# PWR_P3V0_N3V0.net
KiCad netlist of a schematic drawn in Altium Designer
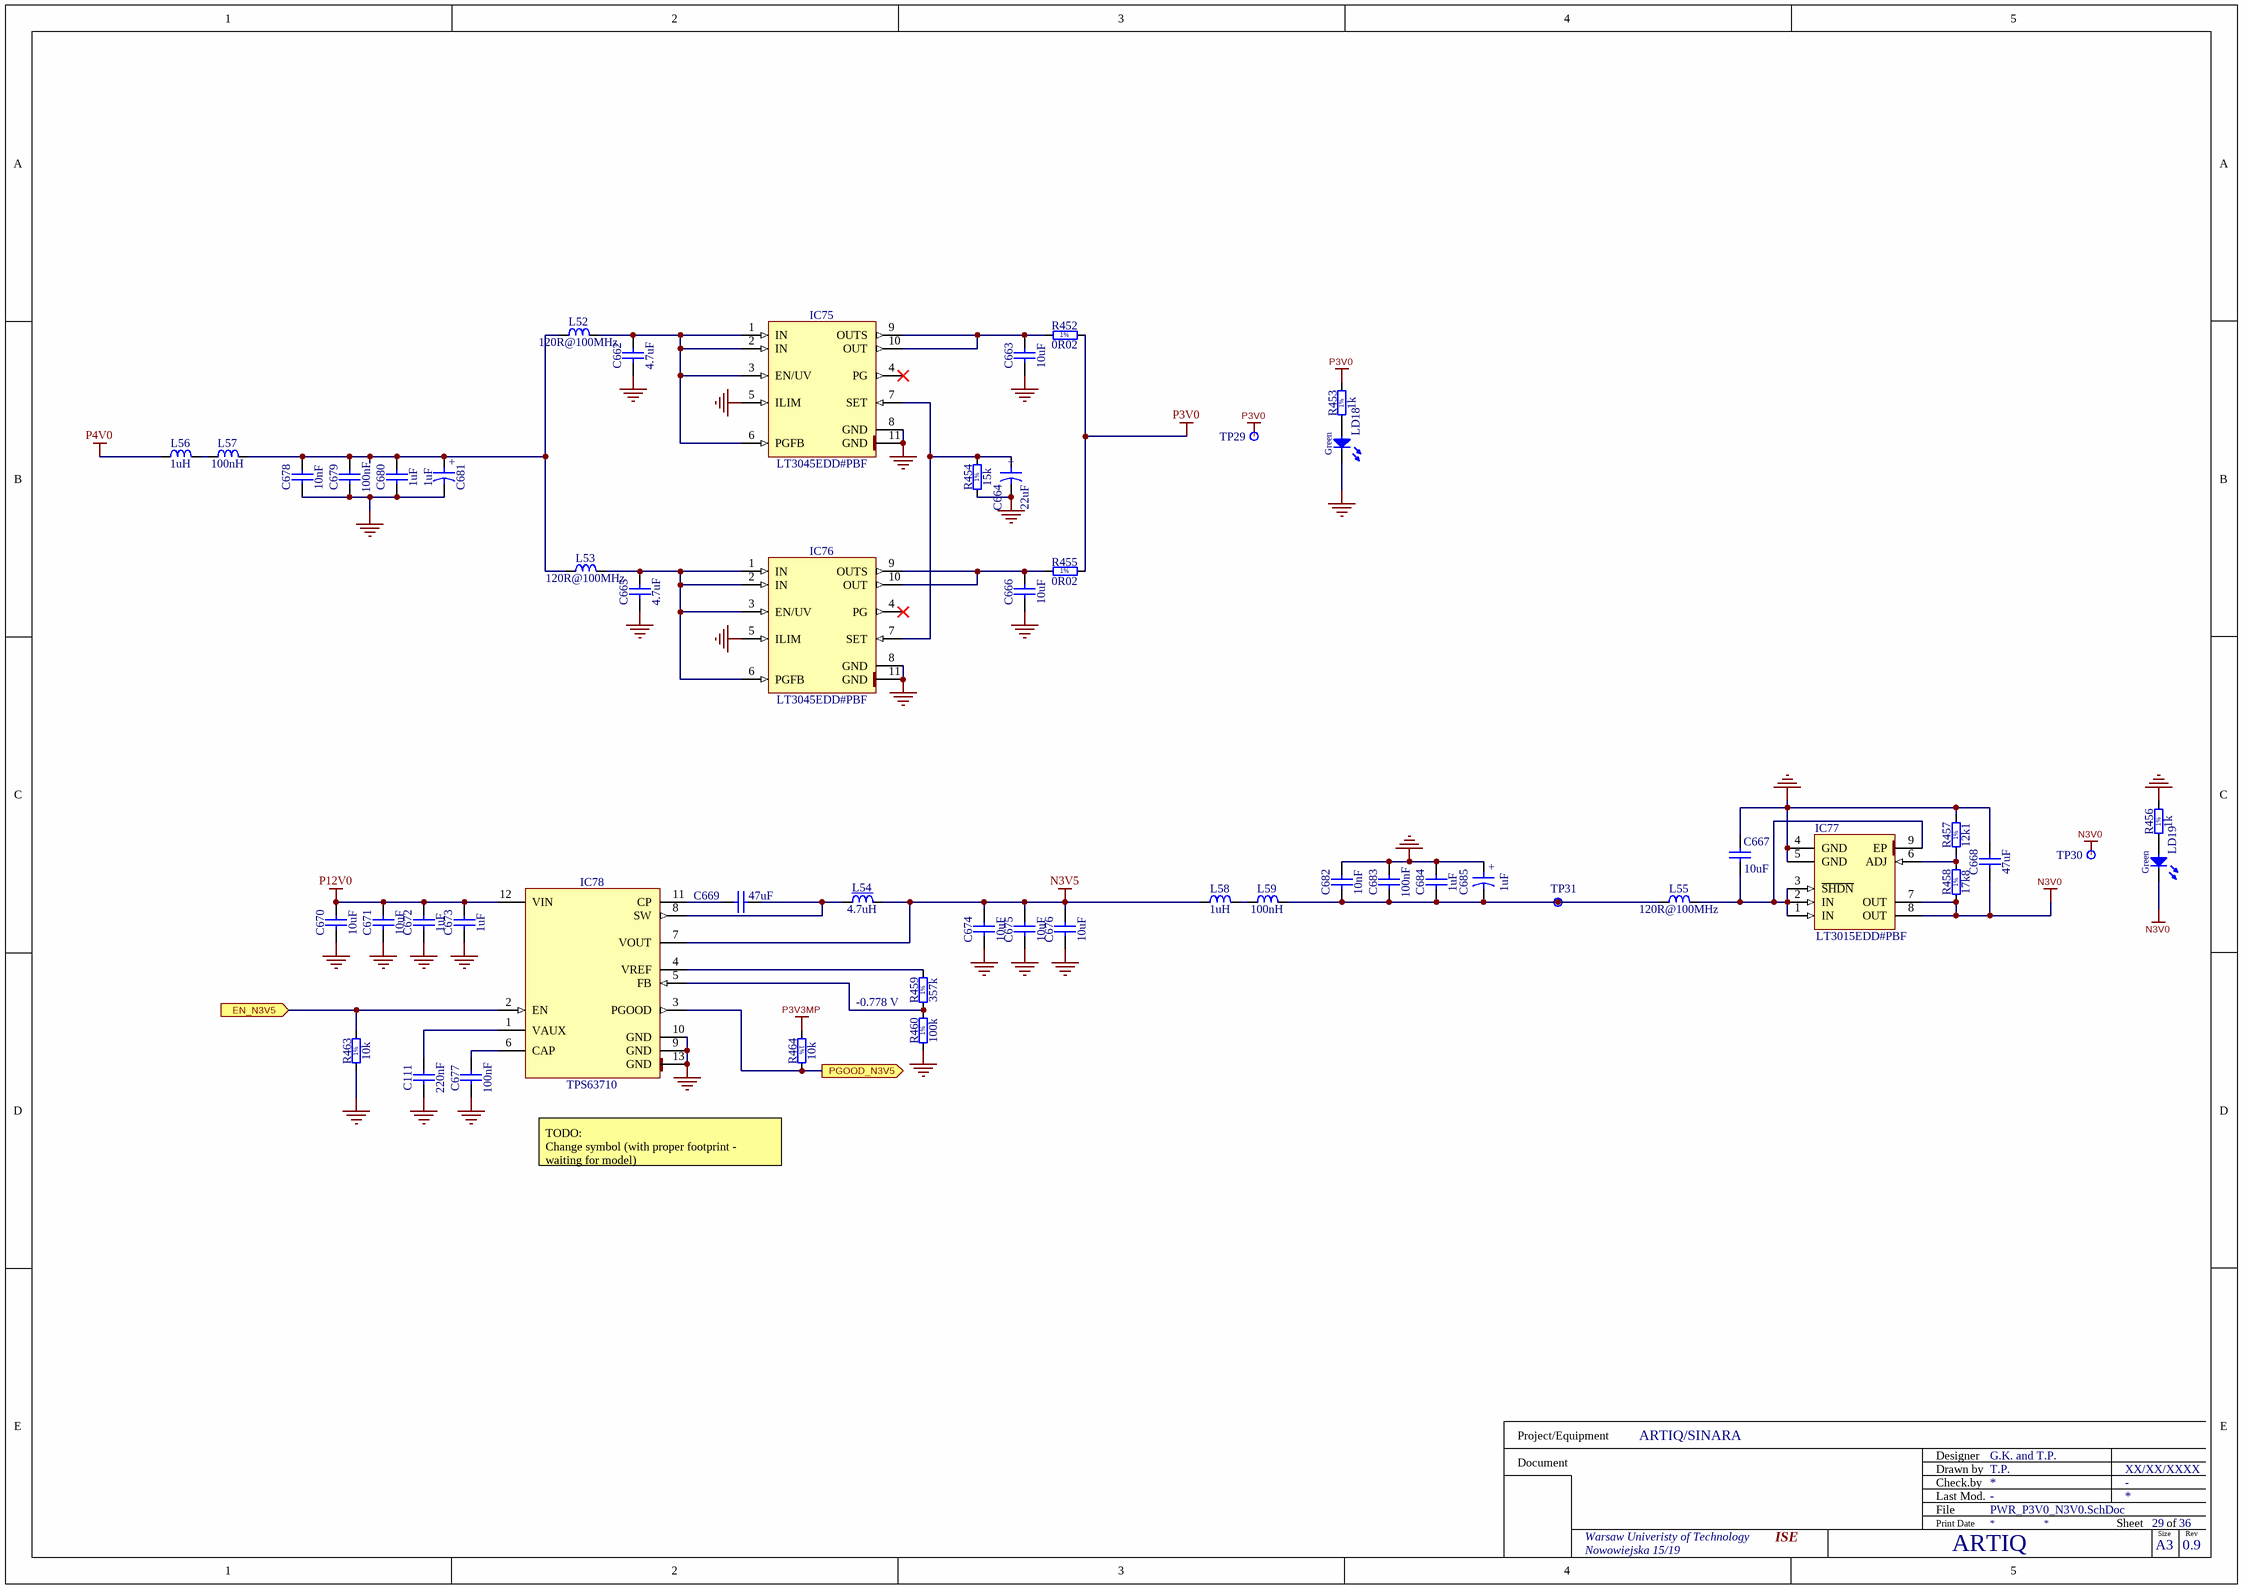
[diagram p0: PWR_P3V0_N3V0.SchDoc]

(export (version "E")
  (design (tool "Eeschema 10.0.6"))
  (components
    (comp (ref "C111")
      (value "220nF")
      (footprint "CAPC0603X33N")
      (description "Non-polarised capacitor")
      (fields
        (field (name "PART NUMBER") "CC0201_220NF_6.3V_20%_X5R")
        (field (name "VOLTAGE") "6.3V")
        (field (name "AUTHOR") "CERN DEM JLC")
      )
      (libsource (lib "Capacitors") (part "Capacitor - non polarized"))
    )
    (comp (ref "C662")
      (value "4.7uF")
      (footprint "CAPC1608X90N")
      (description "Non-polarised capacitor")
      (fields
        (field (name "PART NUMBER") "CC0603_4.7UF_25V_10%_X5R")
        (field (name "VOLTAGE") "25V")
        (field (name "AUTHOR") "CERN DEM JLC")
      )
      (libsource (lib "Capacitors") (part "Capacitor - non polarized"))
    )
    (comp (ref "C663")
      (value "10uF")
      (footprint "CAPC1608X87N")
      (description "Non-polarised capacitor")
      (fields
        (field (name "PART NUMBER") "CC0603_10UF_6.3V_20%_X5R")
        (field (name "VOLTAGE") "6.3V")
        (field (name "AUTHOR") "CERN DEM JLC")
      )
      (libsource (lib "Capacitors") (part "Capacitor - non polarized"))
    )
    (comp (ref "C664")
      (value "22uF")
      (footprint "CAPMP3216X180N")
      (description "Polarised capacitor")
      (fields
        (field (name "PART NUMBER") "CTE3216-18_22UF_6.3V_10%_LESR0900")
        (field (name "VOLTAGE") "6.3V")
        (field (name "AUTHOR") "CERN DEM JLC")
      )
      (libsource (lib "") (part "Capacitor - polarized_1"))
    )
    (comp (ref "C665")
      (value "4.7uF")
      (footprint "CAPC1608X90N")
      (description "Non-polarised capacitor")
      (fields
        (field (name "PART NUMBER") "CC0603_4.7UF_25V_10%_X5R")
        (field (name "VOLTAGE") "25V")
        (field (name "AUTHOR") "CERN DEM JLC")
      )
      (libsource (lib "Capacitors") (part "Capacitor - non polarized"))
    )
    (comp (ref "C666")
      (value "10uF")
      (footprint "CAPC1608X87N")
      (description "Non-polarised capacitor")
      (fields
        (field (name "PART NUMBER") "CC0603_10UF_6.3V_20%_X5R")
        (field (name "VOLTAGE") "6.3V")
        (field (name "AUTHOR") "CERN DEM JLC")
      )
      (libsource (lib "Capacitors") (part "Capacitor - non polarized"))
    )
    (comp (ref "C667")
      (value "10uF")
      (footprint "CAPC3216X180N")
      (description "Non-polarised capacitor")
      (fields
        (field (name "MANUFACTURER PART NUMBER") "CC1206_10uF_25V_10%_X7R")
        (field (name "MANUFACTURER") "GENERIC")
        (field (name "AUTHOR") "CERN DEM JLC")
      )
      (libsource (lib "Capacitors") (part "Capacitor - non polarized"))
    )
    (comp (ref "C668")
      (value "47uF")
      (footprint "CAPC2012X140N")
      (description "Non-polarised capacitor")
      (fields
        (field (name "PART NUMBER") "CC0805_47UF_6.3V_20%_X5R")
        (field (name "VOLTAGE") "6.3V")
        (field (name "AUTHOR") "CERN DEM JLC")
      )
      (libsource (lib "Capacitors") (part "Capacitor - non polarized"))
    )
    (comp (ref "C669")
      (value "47uF")
      (footprint "CAPC3216X180N")
      (description "Non-polarised capacitor")
      (fields
        (field (name "PART NUMBER") "CC1206_47UF_25V_20%_X5R")
        (field (name "VOLTAGE") "25V")
        (field (name "AUTHOR") "CERN DEM JLC")
      )
      (libsource (lib "Capacitors") (part "Capacitor - non polarized"))
    )
    (comp (ref "C670")
      (value "10uF")
      (footprint "CAPC1608X87N")
      (description "Non-polarised capacitor")
      (fields
        (field (name "PART NUMBER") "CC0603_10UF_6.3V_20%_X5R")
        (field (name "VOLTAGE") "6.3V")
        (field (name "AUTHOR") "CERN DEM JLC")
      )
      (libsource (lib "Capacitors") (part "Capacitor - non polarized"))
    )
    (comp (ref "C671")
      (value "10uF")
      (footprint "CAPC1608X87N")
      (description "Non-polarised capacitor")
      (fields
        (field (name "PART NUMBER") "CC0603_10UF_6.3V_20%_X5R")
        (field (name "VOLTAGE") "6.3V")
        (field (name "AUTHOR") "CERN DEM JLC")
      )
      (libsource (lib "Capacitors") (part "Capacitor - non polarized"))
    )
    (comp (ref "C672")
      (value "1uF")
      (footprint "CAPC1005X55N")
      (description "Non-polarised capacitor")
      (fields
        (field (name "MANUFACTURER PART NUMBER") "CC0402_1UF_16V_10%_X5R")
        (field (name "MANUFACTURER") "GENERIC")
        (field (name "AUTHOR") "CERN DEM JLC")
      )
      (libsource (lib "Capacitors") (part "Capacitor - non polarized"))
    )
    (comp (ref "C673")
      (value "1uF")
      (footprint "CAPC1005X55N")
      (description "Non-polarised capacitor")
      (fields
        (field (name "MANUFACTURER PART NUMBER") "CC0402_1UF_16V_10%_X5R")
        (field (name "MANUFACTURER") "GENERIC")
        (field (name "AUTHOR") "CERN DEM JLC")
      )
      (libsource (lib "Capacitors") (part "Capacitor - non polarized"))
    )
    (comp (ref "C674")
      (value "10uF")
      (footprint "CAPC2012X95N")
      (description "Non-polarised capacitor")
      (fields
        (field (name "PART NUMBER") "CC0805_10UF_25V_10%_X5R")
        (field (name "VOLTAGE") "25V")
        (field (name "AUTHOR") "CERN DEM JLC")
      )
      (libsource (lib "Capacitors") (part "Capacitor - non polarized"))
    )
    (comp (ref "C675")
      (value "10uF")
      (footprint "CAPC2012X95N")
      (description "Non-polarised capacitor")
      (fields
        (field (name "PART NUMBER") "CC0805_10UF_25V_10%_X5R")
        (field (name "VOLTAGE") "25V")
        (field (name "AUTHOR") "CERN DEM JLC")
      )
      (libsource (lib "Capacitors") (part "Capacitor - non polarized"))
    )
    (comp (ref "C676")
      (value "10uF")
      (footprint "CAPC2012X95N")
      (description "Non-polarised capacitor")
      (fields
        (field (name "PART NUMBER") "CC0805_10UF_25V_10%_X5R")
        (field (name "VOLTAGE") "25V")
        (field (name "AUTHOR") "CERN DEM JLC")
      )
      (libsource (lib "Capacitors") (part "Capacitor - non polarized"))
    )
    (comp (ref "C677")
      (value "100nF")
      (footprint "CAPC1005X55N")
      (description "Non-polarised capacitor")
      (fields
        (field (name "MANUFACTURER PART NUMBER") "CC0402_100NF_16V_10%_X5R")
        (field (name "MANUFACTURER") "GENERIC")
        (field (name "AUTHOR") "CERN DEM JLC")
      )
      (libsource (lib "Capacitors") (part "Capacitor - non polarized"))
    )
    (comp (ref "C678")
      (value "10nF")
      (footprint "CAPC0603X33N")
      (description "Non-polarised capacitor")
      (fields
        (field (name "PART NUMBER") "CC0201_10NF_10V_10%_X5R")
        (field (name "VOLTAGE") "10V")
        (field (name "AUTHOR") "CERN DEM JLC")
      )
      (libsource (lib "Capacitors") (part "Capacitor - non polarized"))
    )
    (comp (ref "C679")
      (value "100nF")
      (footprint "CAPC0603X33N")
      (description "Non-polarised capacitor")
      (fields
        (field (name "PART NUMBER") "CC0201_100NF_6.3V_10%_X5R")
        (field (name "VOLTAGE") "6.3V")
        (field (name "AUTHOR") "CERN DEM JLC")
      )
      (libsource (lib "Capacitors") (part "Capacitor - non polarized"))
    )
    (comp (ref "C680")
      (value "1uF")
      (footprint "CAPC1005X55N")
      (description "Non-polarised capacitor")
      (fields
        (field (name "PART NUMBER") "CC0402_1UF_16V_10%_X5R")
        (field (name "VOLTAGE") "16V")
        (field (name "AUTHOR") "CERN DEM JLC")
      )
      (libsource (lib "Capacitors") (part "Capacitor - non polarized"))
    )
    (comp (ref "C681")
      (value "1uF")
      (footprint "CAPMP6032X280N")
      (description "Polarised capacitor")
      (fields
        (field (name "PART NUMBER") "CTE6032-28_1UF_50V_10%")
        (field (name "VOLTAGE") "50V")
        (field (name "AUTHOR") "CERN DEM JLC")
      )
      (libsource (lib "Capacitors") (part "Capacitor - polarized"))
    )
    (comp (ref "C682")
      (value "10nF")
      (footprint "CAPC0603X33N")
      (description "Non-polarised capacitor")
      (fields
        (field (name "PART NUMBER") "CC0201_10NF_10V_10%_X5R")
        (field (name "VOLTAGE") "10V")
        (field (name "AUTHOR") "CERN DEM JLC")
      )
      (libsource (lib "Capacitors") (part "Capacitor - non polarized"))
    )
    (comp (ref "C683")
      (value "100nF")
      (footprint "CAPC0603X33N")
      (description "Non-polarised capacitor")
      (fields
        (field (name "PART NUMBER") "CC0201_100NF_6.3V_10%_X5R")
        (field (name "VOLTAGE") "6.3V")
        (field (name "AUTHOR") "CERN DEM JLC")
      )
      (libsource (lib "Capacitors") (part "Capacitor - non polarized"))
    )
    (comp (ref "C684")
      (value "1uF")
      (footprint "CAPC1005X55N")
      (description "Non-polarised capacitor")
      (fields
        (field (name "PART NUMBER") "CC0402_1UF_16V_10%_X5R")
        (field (name "VOLTAGE") "16V")
        (field (name "AUTHOR") "CERN DEM JLC")
      )
      (libsource (lib "Capacitors") (part "Capacitor - non polarized"))
    )
    (comp (ref "C685")
      (value "1uF")
      (footprint "CAPMP6032X280N")
      (description "Polarised capacitor")
      (fields
        (field (name "PART NUMBER") "CTE6032-28_1UF_50V_10%")
        (field (name "VOLTAGE") "50V")
        (field (name "AUTHOR") "CERN DEM JLC")
      )
      (libsource (lib "Capacitors") (part "Capacitor - polarized"))
    )
    (comp (ref "IC75")
      (value "LT3045EDD#PBF")
      (footprint "SON50P300X300X80-11N-R175X248")
      (description "20V, 500mA, Ultralow Noise, Ultrahigh PSRR Linear Regulator")
      (fields (field (name "MANUFACTURER") "LINEAR TECHNOLOGY") (field (name "AUTHOR") "CERN DEM JLC"))
      (libsource (lib "ICs And Semiconductors") (part "LT3045EDD"))
    )
    (comp (ref "IC76")
      (value "LT3045EDD#PBF")
      (footprint "SON50P300X300X80-11N-R175X248")
      (description "20V, 500mA, Ultralow Noise, Ultrahigh PSRR Linear Regulator")
      (fields (field (name "MANUFACTURER") "LINEAR TECHNOLOGY") (field (name "AUTHOR") "CERN DEM JLC"))
      (libsource (lib "ICs And Semiconductors") (part "LT3045EDD"))
    )
    (comp (ref "IC77")
      (value "LT3015EDD#PBF")
      (footprint "SON50P300X300X80-9N-R175X248")
      (description "1.5A, Low Noise, Negative Linear Regulator with Precision Current Limit")
      (fields (field (name "MANUFACTURER") "LINEAR TECHNOLOGY") (field (name "AUTHOR") "CERN DEM MR"))
      (libsource (lib "ICs And Semiconductors") (part "LT3015EDD"))
    )
    (comp (ref "IC78")
      (value "TPS63710")
      (description "3.1V to 14V Input, 1A  Low Noise Synchronous Inverting Buck Converter")
      (fields (field (name "MANUFACTURER") "TEXAS INSTRUMENTS"))
      (libsource (lib "TP_LIB") (part "TPS63710DRR"))
    )
    (comp (ref "L52")
      (value "120R@100MHz")
      (footprint "INDC1608X95N")
      (description "Inductor")
      (fields
        (field (name "PART NUMBER") "IND0603_MURATA_BLM18PG121SN1D")
        (field (name "POWER") "2A")
        (field (name "AUTHOR") "CERN DEM BC")
      )
      (libsource (lib "Inductors & Transformers") (part "Inductor"))
    )
    (comp (ref "L53")
      (value "120R@100MHz")
      (footprint "INDC1608X95N")
      (description "Inductor")
      (fields
        (field (name "PART NUMBER") "IND0603_MURATA_BLM18PG121SN1D")
        (field (name "POWER") "2A")
        (field (name "AUTHOR") "CERN DEM BC")
      )
      (libsource (lib "Inductors & Transformers") (part "Inductor"))
    )
    (comp (ref "L54")
      (value "4.7uH")
      (footprint "IND_WURTH_WE-SPC-4838")
      (description "Inductor With Core")
      (fields
        (field (name "PART NUMBER") "IND_4.7UH_20%_WURTH_WE-SPC_74408943047")
        (field (name "POWER") "2.2A")
        (field (name "AUTHOR") "CERN DEM JLC")
      )
      (libsource (lib "Inductors & Transformers") (part "Inductor With Magnetic core"))
    )
    (comp (ref "L55")
      (value "120R@100MHz")
      (footprint "INDC1608X95N")
      (description "Inductor")
      (fields
        (field (name "PART NUMBER") "IND0603_MURATA_BLM18PG121SN1D")
        (field (name "POWER") "2A")
        (field (name "AUTHOR") "CERN DEM BC")
      )
      (libsource (lib "Inductors & Transformers") (part "Inductor"))
    )
    (comp (ref "L56")
      (value "1uH")
      (footprint "INDC2012X110N")
      (description "Inductor")
      (fields
        (field (name "PART NUMBER") "IND0805_1UH_20%_WURTH_74479775210")
        (field (name "POWER") "800mA")
        (field (name "AUTHOR") "CERN DEM JLC")
      )
      (libsource (lib "Inductors & Transformers") (part "Inductor"))
    )
    (comp (ref "L57")
      (value "100nH")
      (footprint "IND_COILCRAFT_1812SMS")
      (description "Inductor")
      (fields
        (field (name "PART NUMBER") "IND_100NH_5%_COILCRAFT_1812SMS-R10JLC")
        (field (name "POWER") "1.7A")
        (field (name "AUTHOR") "CERN DEM JLC")
      )
      (libsource (lib "Inductors & Transformers") (part "Inductor"))
    )
    (comp (ref "L58")
      (value "1uH")
      (footprint "INDC2012X110N")
      (description "Inductor")
      (fields
        (field (name "PART NUMBER") "IND0805_1UH_20%_WURTH_74479775210")
        (field (name "POWER") "800mA")
        (field (name "AUTHOR") "CERN DEM JLC")
      )
      (libsource (lib "Inductors & Transformers") (part "Inductor"))
    )
    (comp (ref "L59")
      (value "100nH")
      (footprint "IND_COILCRAFT_1812SMS")
      (description "Inductor")
      (fields
        (field (name "PART NUMBER") "IND_100NH_5%_COILCRAFT_1812SMS-R10JLC")
        (field (name "POWER") "1.7A")
        (field (name "AUTHOR") "CERN DEM JLC")
      )
      (libsource (lib "Inductors & Transformers") (part "Inductor"))
    )
    (comp (ref "LD18")
      (value "Green")
      (footprint "LED_OSRAM_LGL29K")
      (description "LED Green 1C 2A")
      (fields
        (field (name "MANUFACTURER PART NUMBER") "LG L29K-G2J1-24-Z")
        (field (name "MANUFACTURER") "OSRAM")
        (field (name "AUTHOR") "CERN DEM JLC")
      )
      (libsource (lib "ICs And Semiconductors") (part "LED Green 1C 2A"))
    )
    (comp (ref "LD19")
      (value "Green")
      (footprint "LED_OSRAM_LGL29K")
      (description "LED Green 1C 2A")
      (fields
        (field (name "MANUFACTURER PART NUMBER") "LG L29K-G2J1-24-Z")
        (field (name "MANUFACTURER") "OSRAM")
        (field (name "AUTHOR") "CERN DEM JLC")
      )
      (libsource (lib "ICs And Semiconductors") (part "LED Green 1C 2A"))
    )
    (comp (ref "R452")
      (value "0R02")
      (footprint "RESC3216X80N")
      (description "Resistor - 1%")
      (fields
        (field (name "PART NUMBER") "R1206_0R02_1%_0.5W_100PPM")
        (field (name "POWER") "0.5W")
        (field (name "AUTHOR") "CERN DEM JLC")
      )
      (libsource (lib "Resistors") (part "Resistor - 1%"))
    )
    (comp (ref "R453")
      (value "1k")
      (footprint "RESC1005X40N")
      (description "Resistor - 1%")
      (fields
        (field (name "MANUFACTURER PART NUMBER") "R0402_1K_1%_0.0625W_100PPM")
        (field (name "MANUFACTURER") "GENERIC")
        (field (name "AUTHOR") "CERN DEM JLC")
      )
      (libsource (lib "Resistors") (part "Resistor - 1%"))
    )
    (comp (ref "R454")
      (value "15k")
      (footprint "RESC1005X40N")
      (description "Resistor - 1%")
      (fields
        (field (name "PART NUMBER") "R0402_15K_1%_0.0625W_100PPM")
        (field (name "POWER") "0.0625W")
        (field (name "AUTHOR") "CERN DEM JMW")
      )
      (libsource (lib "Resistors") (part "Resistor - 1%"))
    )
    (comp (ref "R455")
      (value "0R02")
      (footprint "RESC3216X80N")
      (description "Resistor - 1%")
      (fields
        (field (name "PART NUMBER") "R1206_0R02_1%_0.5W_100PPM")
        (field (name "POWER") "0.5W")
        (field (name "AUTHOR") "CERN DEM JLC")
      )
      (libsource (lib "Resistors") (part "Resistor - 1%"))
    )
    (comp (ref "R456")
      (value "1k")
      (footprint "RESC1005X40N")
      (description "Resistor - 1%")
      (fields
        (field (name "MANUFACTURER PART NUMBER") "R0402_1K_1%_0.0625W_100PPM")
        (field (name "MANUFACTURER") "GENERIC")
        (field (name "AUTHOR") "CERN DEM JLC")
      )
      (libsource (lib "Resistors") (part "Resistor - 1%"))
    )
    (comp (ref "R457")
      (value "12k1")
      (footprint "RESC1005X40N")
      (description "Resistor - 1%")
      (fields
        (field (name "PART NUMBER") "R0402_12K1_1%_0.0625W_100PPM")
        (field (name "POWER") "0.0625W")
        (field (name "AUTHOR") "CERN DEM JLC")
      )
      (libsource (lib "Resistors") (part "Resistor - 1%"))
    )
    (comp (ref "R458")
      (value "17k8")
      (footprint "RESC2012X60N")
      (description "Resistor - 1%")
      (fields
        (field (name "PART NUMBER") "R0805_17K8_1%_0.125W_100PPM")
        (field (name "POWER") "0.125W")
        (field (name "AUTHOR") "CERN DEM JLC")
      )
      (libsource (lib "Resistors") (part "Resistor - 1%"))
    )
    (comp (ref "R459")
      (value "357k")
      (footprint "RESC1005X40N")
      (description "Resistor - 1%")
      (fields
        (field (name "PART NUMBER") "R0402_357K_1%_0.0625W_100PPM")
        (field (name "POWER") "0.0625W")
        (field (name "AUTHOR") "CERN DEM BC")
      )
      (libsource (lib "Resistors") (part "Resistor - 1%"))
    )
    (comp (ref "R460")
      (value "100k")
      (footprint "RESC1005X40N")
      (description "Resistor - 1%")
      (fields
        (field (name "PART NUMBER") "R0402_100K_1%_0.0625W_100PPM")
        (field (name "POWER") "0.0625W")
        (field (name "AUTHOR") "CERN DEM JLC")
      )
      (libsource (lib "Resistors") (part "Resistor - 1%"))
    )
    (comp (ref "R463")
      (value "10k")
      (footprint "RESC1005X40N")
      (description "Resistor - 1%")
      (fields
        (field (name "MANUFACTURER PART NUMBER") "R0402_10K_1%_0.0625W_100PPM")
        (field (name "MANUFACTURER") "GENERIC")
        (field (name "AUTHOR") "CERN DEM JLC")
      )
      (libsource (lib "Resistors") (part "Resistor - 1%"))
    )
    (comp (ref "R464")
      (value "10k")
      (footprint "RESC1005X40N")
      (description "Resistor - 1%")
      (fields
        (field (name "MANUFACTURER PART NUMBER") "R0402_10K_1%_0.0625W_100PPM")
        (field (name "MANUFACTURER") "GENERIC")
        (field (name "AUTHOR") "CERN DEM JLC")
      )
      (libsource (lib "Resistors") (part "Resistor - 1%"))
    )
    (comp (ref "TP29")
      (value "Test Point")
      (footprint "TPS127")
      (fields (field (name "PART NUMBER") "SMD_PAD_1.27X1.27MM") (field (name "AUTHOR") "CERN DEM JLC"))
      (libsource (lib "Eletro-mechanical") (part "Test Point"))
    )
    (comp (ref "TP30")
      (value "Test Point")
      (footprint "TPS127")
      (fields (field (name "PART NUMBER") "SMD_PAD_1.27X1.27MM") (field (name "AUTHOR") "CERN DEM JLC"))
      (libsource (lib "Eletro-mechanical") (part "Test Point"))
    )
    (comp (ref "TP31")
      (value "Test Point")
      (footprint "TPS127")
      (fields (field (name "PART NUMBER") "SMD_PAD_1.27X1.27MM") (field (name "AUTHOR") "CERN DEM JLC"))
      (libsource (lib "Eletro-mechanical") (part "Test Point"))
    )
  )
  (nets
    (net (code "1") (name "/EN_N3V5") (class "Default")
      (node (ref "IC78") (pin "2") (pinfunction "EN_2") (pintype "input"))
      (node (ref "R463") (pin "1") (pinfunction "1_1") (pintype "passive"))
    )
    (net (code "2") (name "/PGOOD_N3V5") (class "Default")
      (node (ref "IC78") (pin "3") (pinfunction "PGOOD_3") (pintype "output"))
      (node (ref "R464") (pin "1") (pinfunction "1_1") (pintype "passive"))
    )
    (net (code "3") (name "GND") (class "Default")
      (node (ref "C111") (pin "1") (pinfunction "1_1") (pintype "passive"))
      (node (ref "C662") (pin "1") (pinfunction "1_1") (pintype "passive"))
      (node (ref "C663") (pin "1") (pinfunction "1_1") (pintype "passive"))
      (node (ref "C664") (pin "2") (pinfunction "2_2") (pintype "passive"))
      (node (ref "C665") (pin "1") (pinfunction "1_1") (pintype "passive"))
      (node (ref "C666") (pin "1") (pinfunction "1_1") (pintype "passive"))
      (node (ref "C667") (pin "2") (pinfunction "2_2") (pintype "passive"))
      (node (ref "C668") (pin "2") (pinfunction "2_2") (pintype "passive"))
      (node (ref "C670") (pin "1") (pinfunction "1_1") (pintype "passive"))
      (node (ref "C671") (pin "1") (pinfunction "1_1") (pintype "passive"))
      (node (ref "C672") (pin "1") (pinfunction "1_1") (pintype "passive"))
      (node (ref "C673") (pin "1") (pinfunction "1_1") (pintype "passive"))
      (node (ref "C674") (pin "1") (pinfunction "1_1") (pintype "passive"))
      (node (ref "C675") (pin "1") (pinfunction "1_1") (pintype "passive"))
      (node (ref "C676") (pin "1") (pinfunction "1_1") (pintype "passive"))
      (node (ref "C677") (pin "1") (pinfunction "1_1") (pintype "passive"))
      (node (ref "C678") (pin "1") (pinfunction "1_1") (pintype "passive"))
      (node (ref "C679") (pin "1") (pinfunction "1_1") (pintype "passive"))
      (node (ref "C680") (pin "1") (pinfunction "1_1") (pintype "passive"))
      (node (ref "C681") (pin "2") (pinfunction "2_2") (pintype "passive"))
      (node (ref "C682") (pin "2") (pinfunction "2_2") (pintype "passive"))
      (node (ref "C683") (pin "2") (pinfunction "2_2") (pintype "passive"))
      (node (ref "C684") (pin "2") (pinfunction "2_2") (pintype "passive"))
      (node (ref "C685") (pin "1") (pinfunction "1_1") (pintype "passive"))
      (node (ref "IC75") (pin "11") (pinfunction "GND_11") (pintype "power_in"))
      (node (ref "IC75") (pin "5") (pinfunction "ILIM_5") (pintype "input"))
      (node (ref "IC75") (pin "8") (pinfunction "GND_8") (pintype "power_in"))
      (node (ref "IC76") (pin "11") (pinfunction "GND_11") (pintype "power_in"))
      (node (ref "IC76") (pin "5") (pinfunction "ILIM_5") (pintype "input"))
      (node (ref "IC76") (pin "8") (pinfunction "GND_8") (pintype "power_in"))
      (node (ref "IC77") (pin "4") (pinfunction "GND_4") (pintype "power_in"))
      (node (ref "IC77") (pin "5") (pinfunction "GND_5") (pintype "power_in"))
      (node (ref "IC78") (pin "10") (pinfunction "GND_10") (pintype "power_in"))
      (node (ref "IC78") (pin "13") (pinfunction "GND_13") (pintype "power_in"))
      (node (ref "IC78") (pin "9") (pinfunction "GND_9") (pintype "power_in"))
      (node (ref "LD18") (pin "1") (pinfunction "C_1") (pintype "passive"))
      (node (ref "R454") (pin "1") (pinfunction "1_1") (pintype "passive"))
      (node (ref "R456") (pin "2") (pinfunction "2_2") (pintype "passive"))
      (node (ref "R457") (pin "2") (pinfunction "2_2") (pintype "passive"))
      (node (ref "R460") (pin "1") (pinfunction "1_1") (pintype "passive"))
      (node (ref "R463") (pin "2") (pinfunction "2_2") (pintype "passive"))
    )
    (net (code "4") (name "N3V0") (class "Default")
      (node (ref "C668") (pin "1") (pinfunction "1_1") (pintype "passive"))
      (node (ref "IC77") (pin "7") (pinfunction "OUT_7") (pintype "power_in"))
      (node (ref "IC77") (pin "8") (pinfunction "OUT_8") (pintype "power_in"))
      (node (ref "LD19") (pin "1") (pinfunction "C_1") (pintype "passive"))
      (node (ref "R458") (pin "1") (pinfunction "1_1") (pintype "passive"))
      (node (ref "TP30") (pin "1") (pinfunction "1_1") (pintype "bidirectional"))
    )
    (net (code "5") (name "N3V5") (class "Default")
      (node (ref "C674") (pin "2") (pinfunction "2_2") (pintype "passive"))
      (node (ref "C675") (pin "2") (pinfunction "2_2") (pintype "passive"))
      (node (ref "C676") (pin "2") (pinfunction "2_2") (pintype "passive"))
      (node (ref "IC78") (pin "7") (pinfunction "VOUT_7") (pintype "power_in"))
      (node (ref "L54") (pin "2") (pinfunction "2_2") (pintype "passive"))
      (node (ref "L58") (pin "1") (pinfunction "1_1") (pintype "passive"))
    )
    (net (code "6") (name "Net-(C678-Pad2)") (class "Default")
      (node (ref "C678") (pin "2") (pinfunction "2_2") (pintype "passive"))
      (node (ref "C679") (pin "2") (pinfunction "2_2") (pintype "passive"))
      (node (ref "C680") (pin "2") (pinfunction "2_2") (pintype "passive"))
      (node (ref "C681") (pin "1") (pinfunction "1_1") (pintype "passive"))
      (node (ref "L52") (pin "1") (pinfunction "1_1") (pintype "passive"))
      (node (ref "L53") (pin "1") (pinfunction "1_1") (pintype "passive"))
      (node (ref "L57") (pin "2") (pinfunction "2_2") (pintype "passive"))
    )
    (net (code "7") (name "Net-(C682-Pad1)") (class "Default")
      (node (ref "C682") (pin "1") (pinfunction "1_1") (pintype "passive"))
      (node (ref "C683") (pin "1") (pinfunction "1_1") (pintype "passive"))
      (node (ref "C684") (pin "1") (pinfunction "1_1") (pintype "passive"))
      (node (ref "C685") (pin "2") (pinfunction "2_2") (pintype "passive"))
      (node (ref "L55") (pin "1") (pinfunction "1_1") (pintype "passive"))
      (node (ref "L59") (pin "2") (pinfunction "2_2") (pintype "passive"))
      (node (ref "TP31") (pin "1") (pinfunction "1_1") (pintype "bidirectional"))
    )
    (net (code "8") (name "Net-(IC75-EN{slash}UV)") (class "Default")
      (node (ref "C662") (pin "2") (pinfunction "2_2") (pintype "passive"))
      (node (ref "IC75") (pin "1") (pinfunction "IN_1") (pintype "input"))
      (node (ref "IC75") (pin "2") (pinfunction "IN_2") (pintype "input"))
      (node (ref "IC75") (pin "3") (pinfunction "EN/UV_3") (pintype "input"))
      (node (ref "IC75") (pin "6") (pinfunction "PGFB_6") (pintype "input"))
      (node (ref "L52") (pin "2") (pinfunction "2_2") (pintype "passive"))
    )
    (net (code "9") (name "Net-(IC75-OUT)") (class "Default")
      (node (ref "C663") (pin "2") (pinfunction "2_2") (pintype "passive"))
      (node (ref "IC75") (pin "10") (pinfunction "OUT_10") (pintype "output"))
      (node (ref "IC75") (pin "9") (pinfunction "OUTS_9") (pintype "output"))
      (node (ref "R452") (pin "1") (pinfunction "1_1") (pintype "passive"))
    )
    (net (code "10") (name "Net-(IC75-SET)") (class "Default")
      (node (ref "C664") (pin "1") (pinfunction "1_1") (pintype "passive"))
      (node (ref "IC75") (pin "7") (pinfunction "SET_7") (pintype "input"))
      (node (ref "IC76") (pin "7") (pinfunction "SET_7") (pintype "input"))
      (node (ref "R454") (pin "2") (pinfunction "2_2") (pintype "passive"))
    )
    (net (code "11") (name "Net-(IC76-EN{slash}UV)") (class "Default")
      (node (ref "C665") (pin "2") (pinfunction "2_2") (pintype "passive"))
      (node (ref "IC76") (pin "1") (pinfunction "IN_1") (pintype "input"))
      (node (ref "IC76") (pin "2") (pinfunction "IN_2") (pintype "input"))
      (node (ref "IC76") (pin "3") (pinfunction "EN/UV_3") (pintype "input"))
      (node (ref "IC76") (pin "6") (pinfunction "PGFB_6") (pintype "input"))
      (node (ref "L53") (pin "2") (pinfunction "2_2") (pintype "passive"))
    )
    (net (code "12") (name "Net-(IC76-OUT)") (class "Default")
      (node (ref "C666") (pin "2") (pinfunction "2_2") (pintype "passive"))
      (node (ref "IC76") (pin "10") (pinfunction "OUT_10") (pintype "output"))
      (node (ref "IC76") (pin "9") (pinfunction "OUTS_9") (pintype "output"))
      (node (ref "R455") (pin "1") (pinfunction "1_1") (pintype "passive"))
    )
    (net (code "13") (name "Net-(IC77-ADJ)") (class "Default")
      (node (ref "IC77") (pin "6") (pinfunction "ADJ_6") (pintype "input"))
      (node (ref "R457") (pin "1") (pinfunction "1_1") (pintype "passive"))
      (node (ref "R458") (pin "2") (pinfunction "2_2") (pintype "passive"))
    )
    (net (code "14") (name "Net-(IC77-EP)") (class "Default")
      (node (ref "C667") (pin "1") (pinfunction "1_1") (pintype "passive"))
      (node (ref "IC77") (pin "1") (pinfunction "IN_1") (pintype "input"))
      (node (ref "IC77") (pin "2") (pinfunction "IN_2") (pintype "input"))
      (node (ref "IC77") (pin "3") (pinfunction "~{SHDN}_3") (pintype "input"))
      (node (ref "IC77") (pin "9") (pinfunction "EP_9") (pintype "power_in"))
      (node (ref "L55") (pin "2") (pinfunction "2_2") (pintype "passive"))
    )
    (net (code "15") (name "Net-(IC78-CAP)") (class "Default")
      (node (ref "C677") (pin "2") (pinfunction "2_2") (pintype "passive"))
      (node (ref "IC78") (pin "6") (pinfunction "CAP_6") (pintype "power_in"))
    )
    (net (code "16") (name "Net-(IC78-CP)") (class "Default")
      (node (ref "C669") (pin "1") (pinfunction "1_1") (pintype "passive"))
      (node (ref "IC78") (pin "11") (pinfunction "CP_11") (pintype "power_in"))
    )
    (net (code "17") (name "Net-(IC78-FB)") (class "Default")
      (node (ref "IC78") (pin "5") (pinfunction "FB_5") (pintype "input"))
      (node (ref "R459") (pin "1") (pinfunction "1_1") (pintype "passive"))
      (node (ref "R460") (pin "2") (pinfunction "2_2") (pintype "passive"))
    )
    (net (code "18") (name "Net-(IC78-SW)") (class "Default")
      (node (ref "C669") (pin "2") (pinfunction "2_2") (pintype "passive"))
      (node (ref "IC78") (pin "8") (pinfunction "SW_8") (pintype "output"))
      (node (ref "L54") (pin "1") (pinfunction "1_1") (pintype "passive"))
    )
    (net (code "19") (name "Net-(IC78-VAUX)") (class "Default")
      (node (ref "C111") (pin "2") (pinfunction "2_2") (pintype "passive"))
      (node (ref "IC78") (pin "1") (pinfunction "VAUX_1") (pintype "power_in"))
    )
    (net (code "20") (name "Net-(IC78-VREF)") (class "Default")
      (node (ref "IC78") (pin "4") (pinfunction "VREF_4") (pintype "power_in"))
      (node (ref "R459") (pin "2") (pinfunction "2_2") (pintype "passive"))
    )
    (net (code "21") (name "Net-(L56-Pad2)") (class "Default")
      (node (ref "L56") (pin "2") (pinfunction "2_2") (pintype "passive"))
      (node (ref "L57") (pin "1") (pinfunction "1_1") (pintype "passive"))
    )
    (net (code "22") (name "Net-(L58-Pad2)") (class "Default")
      (node (ref "L58") (pin "2") (pinfunction "2_2") (pintype "passive"))
      (node (ref "L59") (pin "1") (pinfunction "1_1") (pintype "passive"))
    )
    (net (code "23") (name "Net-(LD18-A)") (class "Default")
      (node (ref "LD18") (pin "2") (pinfunction "A_2") (pintype "passive"))
      (node (ref "R453") (pin "1") (pinfunction "1_1") (pintype "passive"))
    )
    (net (code "24") (name "Net-(LD19-A)") (class "Default")
      (node (ref "LD19") (pin "2") (pinfunction "A_2") (pintype "passive"))
      (node (ref "R456") (pin "1") (pinfunction "1_1") (pintype "passive"))
    )
    (net (code "25") (name "P3V0") (class "Default")
      (node (ref "R452") (pin "2") (pinfunction "2_2") (pintype "passive"))
      (node (ref "R453") (pin "2") (pinfunction "2_2") (pintype "passive"))
      (node (ref "R455") (pin "2") (pinfunction "2_2") (pintype "passive"))
      (node (ref "TP29") (pin "1") (pinfunction "1_1") (pintype "bidirectional"))
    )
    (net (code "26") (name "P3V3MP") (class "Default")
      (node (ref "R464") (pin "2") (pinfunction "2_2") (pintype "passive"))
    )
    (net (code "27") (name "P4V0") (class "Default")
      (node (ref "L56") (pin "1") (pinfunction "1_1") (pintype "passive"))
    )
    (net (code "28") (name "P12V0") (class "Default")
      (node (ref "C670") (pin "2") (pinfunction "2_2") (pintype "passive"))
      (node (ref "C671") (pin "2") (pinfunction "2_2") (pintype "passive"))
      (node (ref "C672") (pin "2") (pinfunction "2_2") (pintype "passive"))
      (node (ref "C673") (pin "2") (pinfunction "2_2") (pintype "passive"))
      (node (ref "IC78") (pin "12") (pinfunction "VIN_12") (pintype "power_in"))
    )
    (net (code "29") (name "unconnected-(IC75-PG-Pad4)") (class "Default")
      (node (ref "IC75") (pin "4") (pinfunction "PG_4") (pintype "output+no_connect"))
    )
    (net (code "30") (name "unconnected-(IC76-PG-Pad4)") (class "Default")
      (node (ref "IC76") (pin "4") (pinfunction "PG_4") (pintype "output+no_connect"))
    )
  )
)
